# dc-dc.net
KiCad netlist of a schematic drawn in Altium Designer
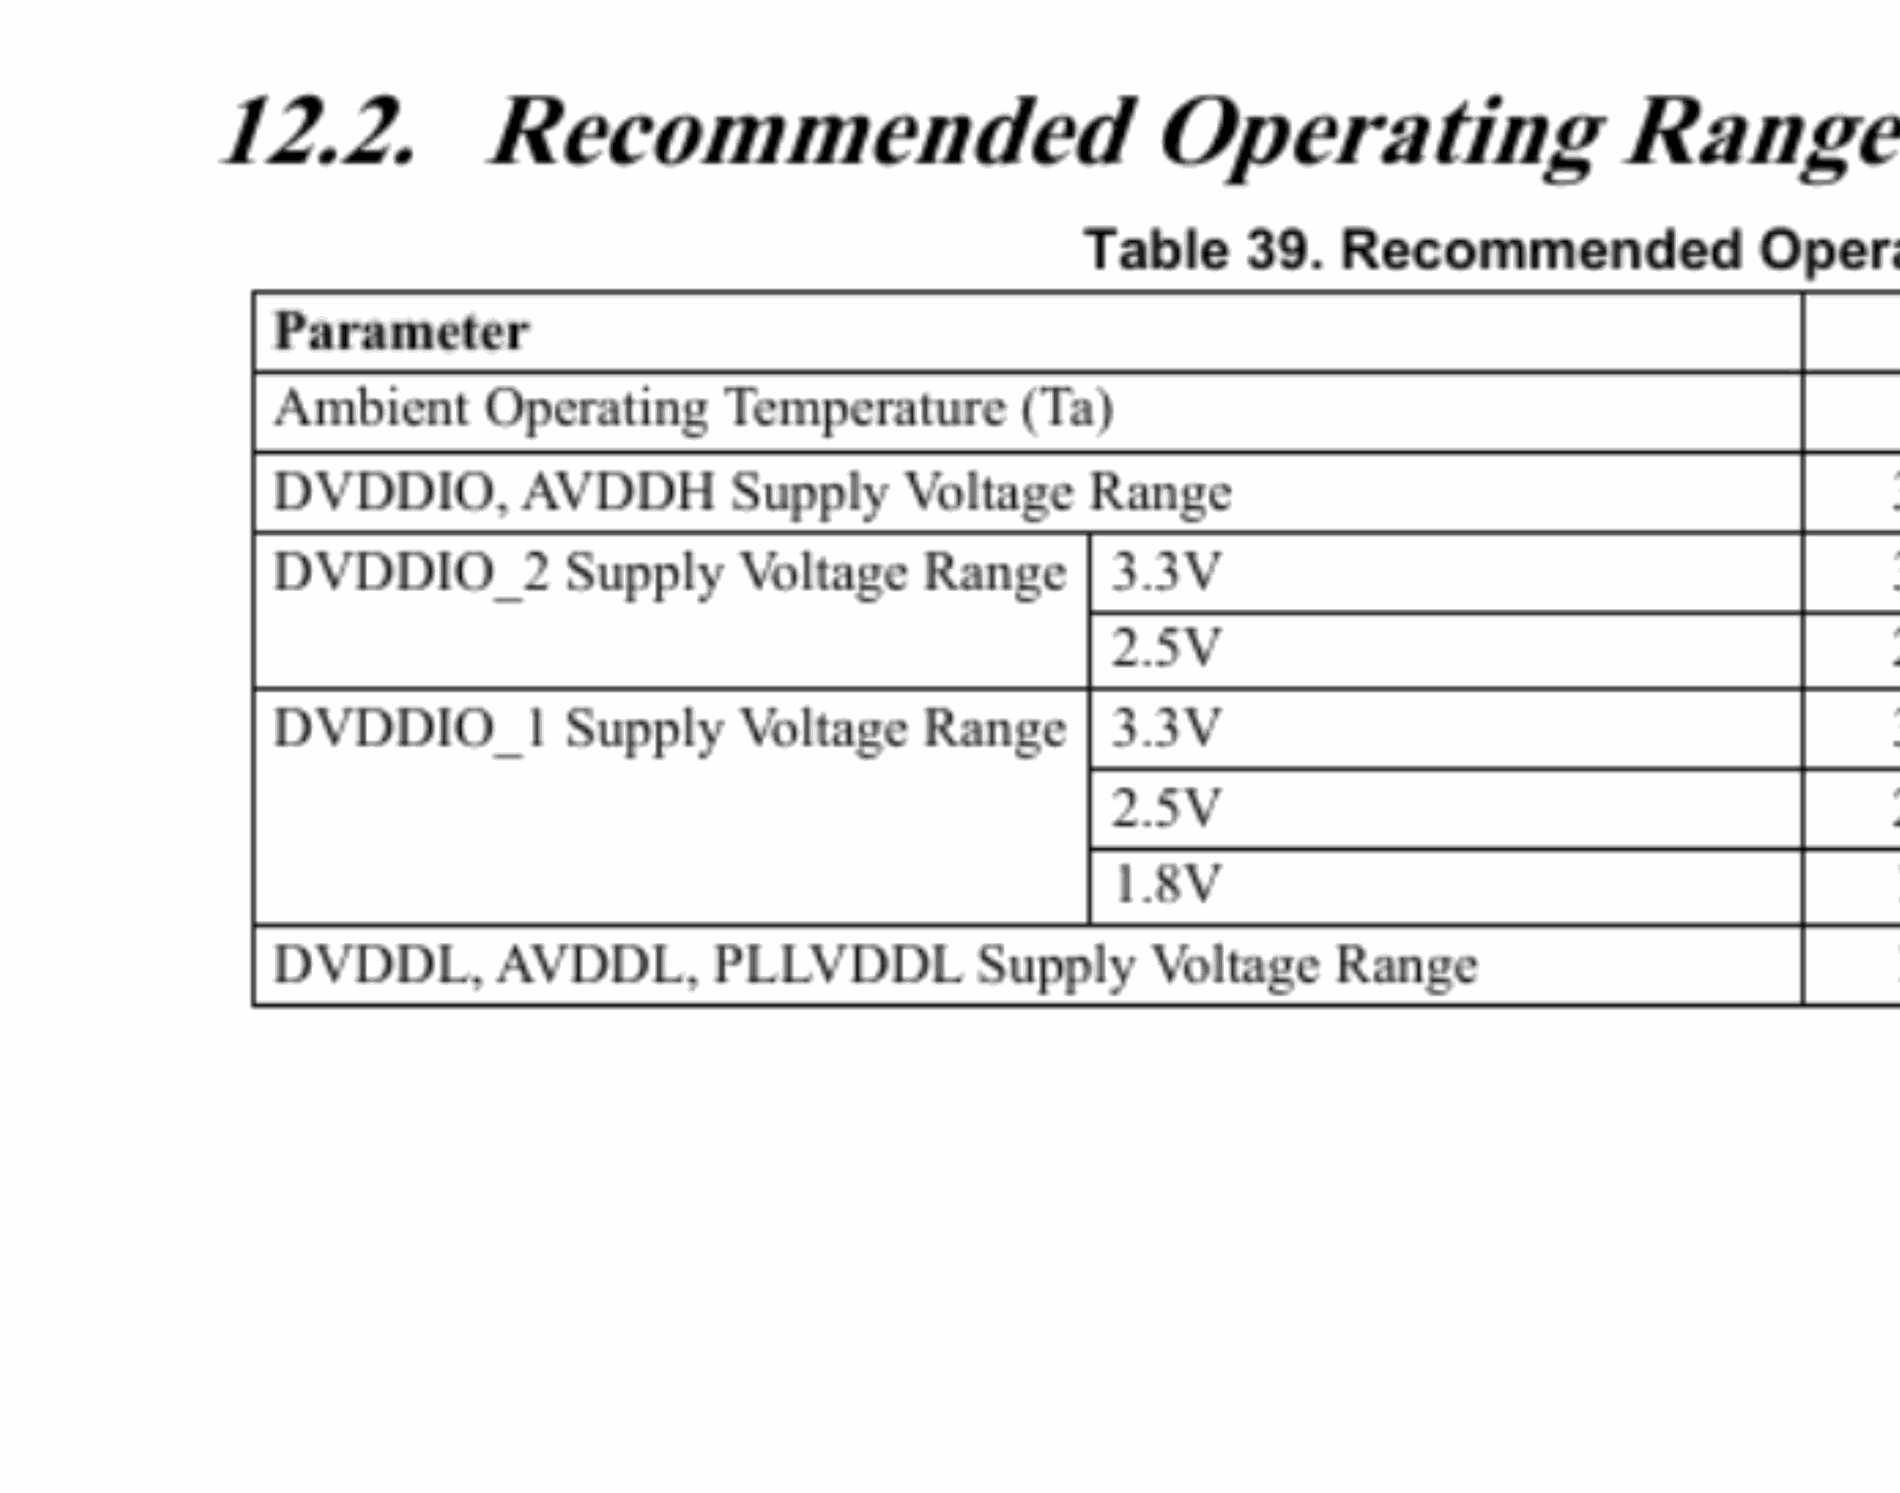
[diagram p0: dc-dc.SchDoc, top left]
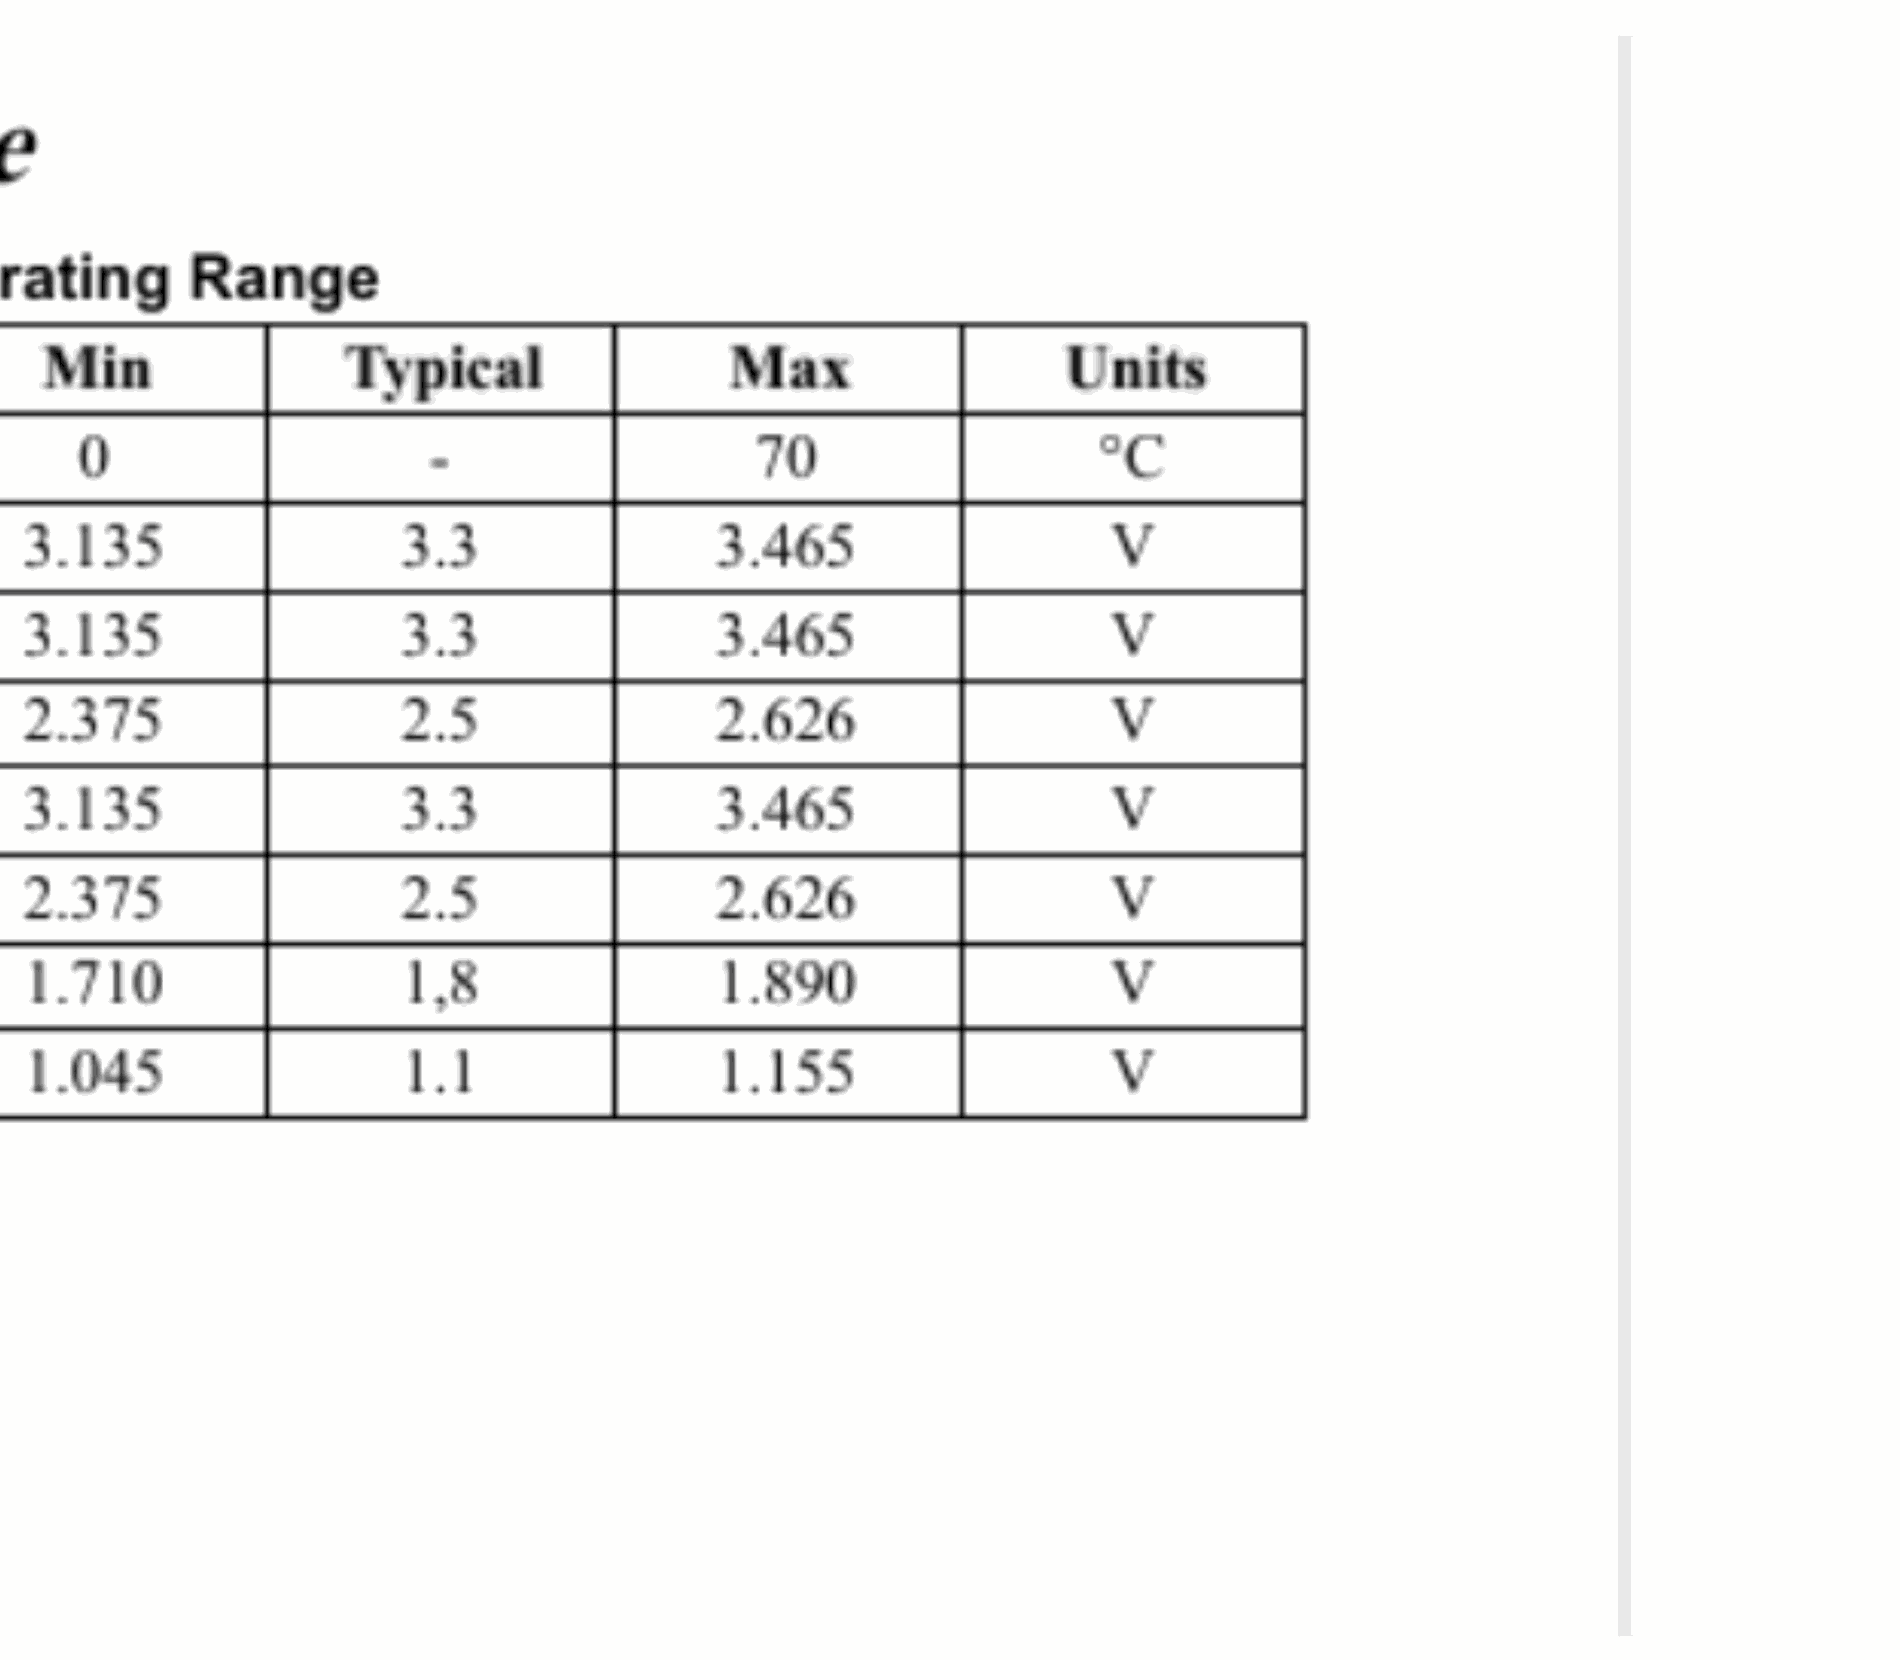
[diagram p1: dc-dc.SchDoc, top right]
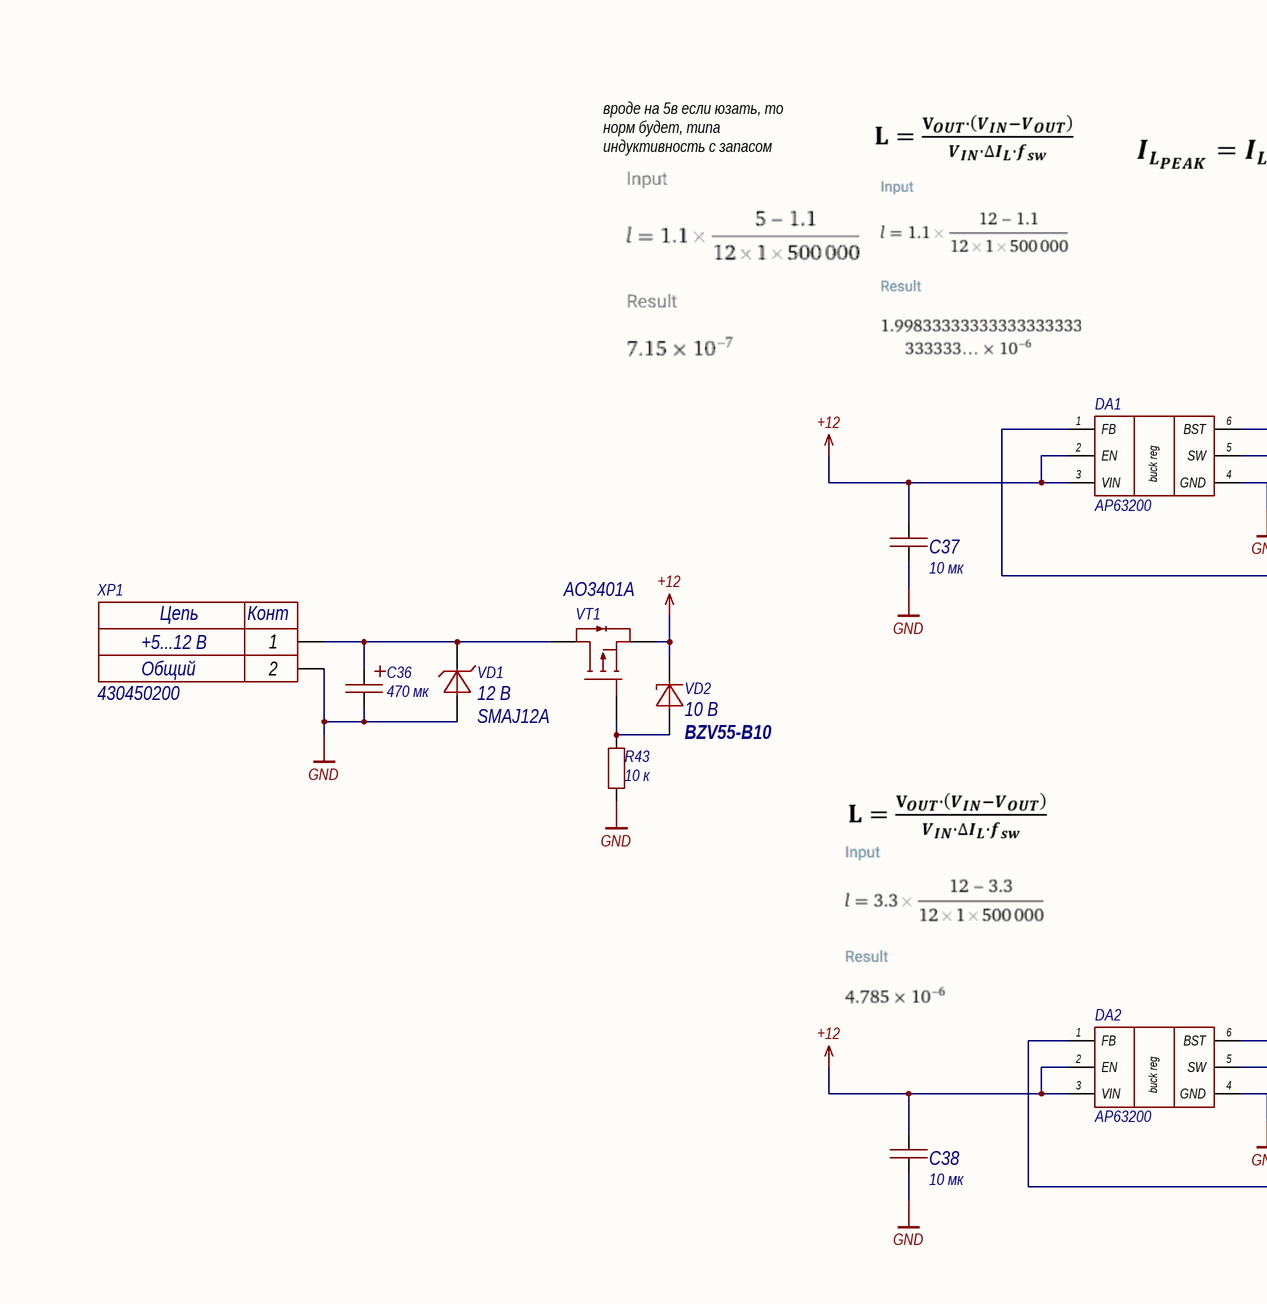
[diagram p2: dc-dc.SchDoc, bottom left]
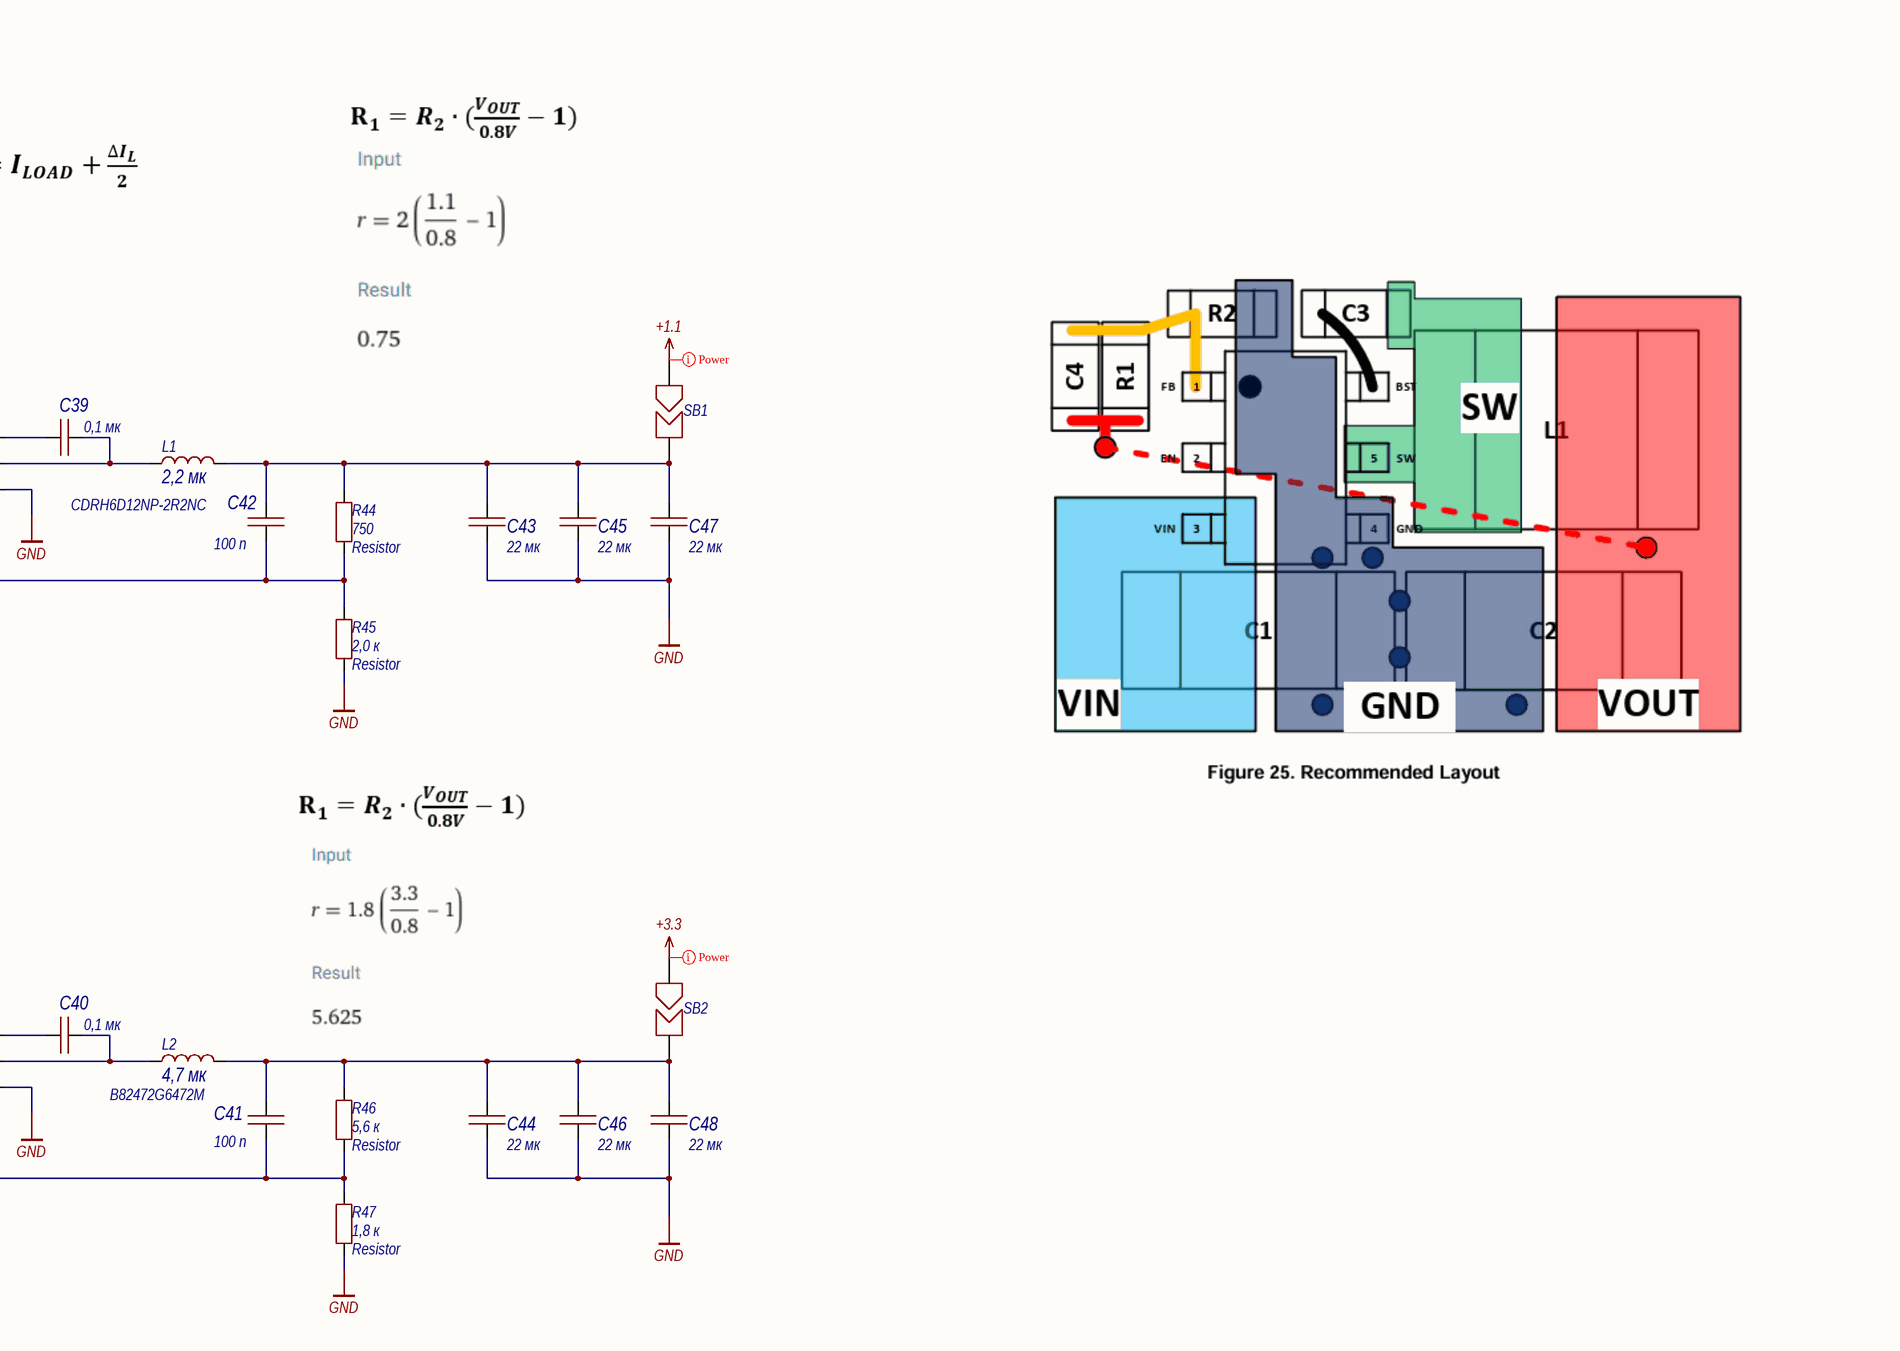
[diagram p3: dc-dc.SchDoc, bottom right]

(export (version "E")
  (design (tool "Eeschema 10.0.6"))
  (components
    (comp (ref "C36")
      (value "470 мк")
      (footprint "ECAP_SMD_10,3x10,3")
      (description "Конденсатор алюминиевый электролитический 470мкФ 16В ±20% (10х10)мм SMD 460мА 2000часов 105°C")
      (fields
        (field (name "PART NUMBER") "CK016M471G10PKKKV00R")
        (field (name "TOLERANCE") "20")
        (field (name "АВТОР") "rreali")
      )
      (libsource (lib "Hydrolib") (part "Capacitor_polar"))
    )
    (comp (ref "C37")
      (value "10 мк")
      (footprint "1210C")
      (description "Конденсатор 1210C ёмкостью 10 мк 10%, 35 В, X7R")
      (fields (field (name "PART NUMBER") "Capacitor_10u_10_35V_X7R_1210C") (field (name "TOLERANCE") "10%"))
      (libsource (lib "Hydrolib") (part "Capacitor"))
    )
    (comp (ref "C38")
      (value "10 мк")
      (footprint "1210C")
      (description "Конденсатор 1210C ёмкостью 10 мк 10%, 35 В, X7R")
      (fields (field (name "PART NUMBER") "Capacitor_10u_10_35V_X7R_1210C") (field (name "TOLERANCE") "10%"))
      (libsource (lib "Hydrolib") (part "Capacitor"))
    )
    (comp (ref "C39")
      (value "0,1 мк")
      (footprint "0603C")
      (description "Конденсатор 0603C ёмкостью 0,1 мк 10%, 50 В, X7R")
      (fields (field (name "PART NUMBER") "Capacitor_0,1u_10_50V_X7R_0603C") (field (name "TOLERANCE") "10%"))
      (libsource (lib "Hydrolib") (part "Capacitor"))
    )
    (comp (ref "C40")
      (value "0,1 мк")
      (footprint "0603C")
      (description "Конденсатор 0603C ёмкостью 0,1 мк 10%, 50 В, X7R")
      (fields (field (name "PART NUMBER") "Capacitor_0,1u_10_50V_X7R_0603C") (field (name "TOLERANCE") "10%"))
      (libsource (lib "Hydrolib") (part "Capacitor"))
    )
    (comp (ref "C41")
      (value "100 п")
      (footprint "0603C")
      (description "Конденсатор 0603C ёмкостью 100 п 10%, 50 В, X7R")
      (fields (field (name "PART NUMBER") "Capacitor_100p_10_50V_X7R_0603C") (field (name "TOLERANCE") "10%"))
      (libsource (lib "Hydrolib") (part "Capacitor"))
    )
    (comp (ref "C42")
      (value "100 п")
      (footprint "0603C")
      (description "Конденсатор 0603C ёмкостью 100 п 10%, 50 В, X7R")
      (fields (field (name "PART NUMBER") "Capacitor_100p_10_50V_X7R_0603C") (field (name "TOLERANCE") "10%"))
      (libsource (lib "Hydrolib") (part "Capacitor"))
    )
    (comp (ref "C43")
      (value "22 мк")
      (footprint "1210C")
      (description "Конденсатор 1210C ёмкостью 22 мк 10%, 25 В, X7R")
      (fields (field (name "PART NUMBER") "Capacitor_22u_10_25V_X7R_1210C") (field (name "TOLERANCE") "10%"))
      (libsource (lib "Hydrolib") (part "Capacitor"))
    )
    (comp (ref "C44")
      (value "22 мк")
      (footprint "1210C")
      (description "Конденсатор 1210C ёмкостью 22 мк 10%, 25 В, X7R")
      (fields (field (name "PART NUMBER") "Capacitor_22u_10_25V_X7R_1210C") (field (name "TOLERANCE") "10%"))
      (libsource (lib "Hydrolib") (part "Capacitor"))
    )
    (comp (ref "C45")
      (value "22 мк")
      (footprint "1210C")
      (description "Конденсатор 1210C ёмкостью 22 мк 10%, 25 В, X7R")
      (fields (field (name "PART NUMBER") "Capacitor_22u_10_25V_X7R_1210C") (field (name "TOLERANCE") "10%"))
      (libsource (lib "Hydrolib") (part "Capacitor"))
    )
    (comp (ref "C46")
      (value "22 мк")
      (footprint "1210C")
      (description "Конденсатор 1210C ёмкостью 22 мк 10%, 25 В, X7R")
      (fields (field (name "PART NUMBER") "Capacitor_22u_10_25V_X7R_1210C") (field (name "TOLERANCE") "10%"))
      (libsource (lib "Hydrolib") (part "Capacitor"))
    )
    (comp (ref "C47")
      (value "22 мк")
      (footprint "1210C")
      (description "Конденсатор 1210C ёмкостью 22 мк 10%, 25 В, X7R")
      (fields (field (name "PART NUMBER") "Capacitor_22u_10_25V_X7R_1210C") (field (name "TOLERANCE") "10%"))
      (libsource (lib "Hydrolib") (part "Capacitor"))
    )
    (comp (ref "C48")
      (value "22 мк")
      (footprint "1210C")
      (description "Конденсатор 1210C ёмкостью 22 мк 10%, 25 В, X7R")
      (fields (field (name "PART NUMBER") "Capacitor_22u_10_25V_X7R_1210C") (field (name "TOLERANCE") "10%"))
      (libsource (lib "Hydrolib") (part "Capacitor"))
    )
    (comp (ref "DA1")
      (value "AP63200")
      (footprint "TSOT26")
      (description "DC-DC понижающий преобразователь, Vin: 3.8 - 40 В, adj, 2 А")
      (libsource (lib "Hydrolib") (part "AP63200"))
    )
    (comp (ref "DA2")
      (value "AP63200")
      (footprint "TSOT26")
      (description "DC-DC понижающий преобразователь, Vin: 3.8 - 40 В, adj, 2 А")
      (libsource (lib "Hydrolib") (part "AP63200"))
    )
    (comp (ref "L1")
      (value "CDRH6D12NP-2R2NC")
      (footprint "CDRH6D12")
      (description "Индуктивность на 2,2 мкГн, номинальный ток 2,5 А")
      (fields (field (name "ALTIUM_VALUE") "2,2 мк") (field (name "АВТОР") "rreali"))
      (libsource (lib "Hydrolib") (part "Inductance_1-3"))
    )
    (comp (ref "L2")
      (value "B82472G6472M")
      (footprint "B82462G4")
      (description "Индуктивность на 4,7 мкГн, номинальный ток 2,5 А")
      (fields (field (name "ALTIUM_VALUE") "4,7 мк") (field (name "АВТОР") "rreali"))
      (libsource (lib "Hydrolib") (part "Inductance"))
    )
    (comp (ref "R43")
      (value "10 к")
      (footprint "0603R")
      (description "Резистор номиналом 10 кОм 1%")
      (fields (field (name "PART NUMBER") "Resistor_10k_1_0603") (field (name "TOLERANCE") "1%"))
      (libsource (lib "Hydrolib") (part "Resistor"))
    )
    (comp (ref "R44")
      (value "Resistor")
      (footprint "0603R")
      (description "Резистор номиналом 750 Ом 1%")
      (fields
        (field (name "ALTIUM_VALUE") "750")
        (field (name "PART NUMBER") "Resistor_750_1_0603")
        (field (name "TOLERANCE") "1%")
      )
      (libsource (lib "Hydrolib") (part "Resistor"))
    )
    (comp (ref "R45")
      (value "Resistor")
      (footprint "0603R")
      (description "Резистор номиналом 2,0 кОм 1%")
      (fields
        (field (name "ALTIUM_VALUE") "2,0 к")
        (field (name "PART NUMBER") "Resistor_2.0k_1_0603")
        (field (name "TOLERANCE") "1%")
      )
      (libsource (lib "Hydrolib") (part "Resistor"))
    )
    (comp (ref "R46")
      (value "Resistor")
      (footprint "0603R")
      (description "Резистор номиналом 5,6 кОм 1%")
      (fields
        (field (name "ALTIUM_VALUE") "5,6 к")
        (field (name "PART NUMBER") "Resistor_5.6k_1_0603")
        (field (name "TOLERANCE") "1%")
      )
      (libsource (lib "Hydrolib") (part "Resistor"))
    )
    (comp (ref "R47")
      (value "Resistor")
      (footprint "0603R")
      (description "Резистор номиналом 1,8 кОм 1%")
      (fields
        (field (name "ALTIUM_VALUE") "1,8 к")
        (field (name "PART NUMBER") "Resistor_1.8k_1_0603")
        (field (name "TOLERANCE") "1%")
      )
      (libsource (lib "Hydrolib") (part "Resistor"))
    )
    (comp (ref "SB1")
      (value "SB")
      (footprint "0805SB")
      (description "Solder bridge, мост припоя, запаиваемая перемычка, net tie, jumper")
      (fields (field (name "АВТОР") "rreali"))
      (libsource (lib "Hydrolib") (part "SB"))
    )
    (comp (ref "SB2")
      (value "SB")
      (footprint "0805SB")
      (description "Solder bridge, мост припоя, запаиваемая перемычка, net tie, jumper")
      (fields (field (name "АВТОР") "rreali"))
      (libsource (lib "Hydrolib") (part "SB"))
    )
    (comp (ref "VD1")
      (value "SMAJ12A")
      (footprint "SMA")
      (description "Защитный диод на 12 В, рассеиваемая мощность 400 Вт")
      (fields (field (name "ALTIUM_VALUE") "12 В") (field (name "АВТОР") "rreali"))
      (libsource (lib "Hydrolib") (part "TVS_1_1dir"))
    )
    (comp (ref "VD2")
      (value "BZV55-B10")
      (footprint "mini_MELF_3.5mm")
      (description "Стабилитрон 10В, 2%, 0.5Вт")
      (fields (field (name "ALTIUM_VALUE") "10 В") (field (name "АВТОР") "rreali"))
      (libsource (lib "Hydrolib") (part "Zener"))
    )
    (comp (ref "VT1")
      (value "AO3401A")
      (footprint "SOT23-3")
      (description "P-канальный MOSFET")
      (libsource (lib "Hydrolib") (part "MOSFET P-channel 2"))
    )
    (comp (ref "XP1")
      (value "430450200")
      (footprint "MOLEX_MICRO-FIT_430450200")
      (fields
        (field (name "VALUE2") "Общий")
        (field (name "VALUE1") "+5...12 В")
        (field (name "АВТОР") "rreali")
      )
      (libsource (lib "Hydrolib") (part "Conn_2pin"))
    )
  )
  (nets
    (net (code "1") (name "+1.1") (class "Default")
      (node (ref "SB1") (pin "1") (pinfunction "1_1") (pintype "passive"))
    )
    (net (code "2") (name "+3.3") (class "Default")
      (node (ref "SB2") (pin "1") (pinfunction "1_1") (pintype "passive"))
    )
    (net (code "3") (name "+12") (class "Default")
      (node (ref "C37") (pin "2") (pinfunction "2_2") (pintype "passive"))
      (node (ref "C38") (pin "2") (pinfunction "2_2") (pintype "passive"))
      (node (ref "DA1") (pin "2") (pinfunction "EN_2") (pintype "passive"))
      (node (ref "DA1") (pin "3") (pinfunction "VIN_3") (pintype "passive"))
      (node (ref "DA2") (pin "2") (pinfunction "EN_2") (pintype "passive"))
      (node (ref "DA2") (pin "3") (pinfunction "VIN_3") (pintype "passive"))
      (node (ref "VD2") (pin "2") (pinfunction "2_2") (pintype "passive"))
      (node (ref "VT1") (pin "2") (pinfunction "2_2") (pintype "passive"))
    )
    (net (code "4") (name "GND") (class "Default")
      (node (ref "C36") (pin "2") (pinfunction "2_2") (pintype "passive"))
      (node (ref "C37") (pin "1") (pinfunction "1_1") (pintype "passive"))
      (node (ref "C38") (pin "1") (pinfunction "1_1") (pintype "passive"))
      (node (ref "C43") (pin "1") (pinfunction "1_1") (pintype "passive"))
      (node (ref "C44") (pin "1") (pinfunction "1_1") (pintype "passive"))
      (node (ref "C45") (pin "1") (pinfunction "1_1") (pintype "passive"))
      (node (ref "C46") (pin "1") (pinfunction "1_1") (pintype "passive"))
      (node (ref "C47") (pin "1") (pinfunction "1_1") (pintype "passive"))
      (node (ref "C48") (pin "1") (pinfunction "1_1") (pintype "passive"))
      (node (ref "DA1") (pin "4") (pinfunction "GND_4") (pintype "passive"))
      (node (ref "DA2") (pin "4") (pinfunction "GND_4") (pintype "passive"))
      (node (ref "R43") (pin "1") (pinfunction "1_1") (pintype "passive"))
      (node (ref "R45") (pin "1") (pinfunction "1_1") (pintype "passive"))
      (node (ref "R47") (pin "1") (pinfunction "1_1") (pintype "passive"))
      (node (ref "VD1") (pin "1") (pinfunction "1_1") (pintype "passive"))
      (node (ref "XP1") (pin "2") (pinfunction "2_2") (pintype "passive"))
    )
    (net (code "5") (name "Net-(C36-Pad1)") (class "Default")
      (node (ref "C36") (pin "1") (pinfunction "1_1") (pintype "passive"))
      (node (ref "VD1") (pin "2") (pinfunction "2_2") (pintype "passive"))
      (node (ref "VT1") (pin "3") (pinfunction "3_3") (pintype "passive"))
      (node (ref "XP1") (pin "1") (pinfunction "1_1") (pintype "passive"))
    )
    (net (code "6") (name "Net-(C41-Pad2)") (class "Default")
      (node (ref "C41") (pin "2") (pinfunction "2_2") (pintype "passive"))
      (node (ref "C44") (pin "2") (pinfunction "2_2") (pintype "passive"))
      (node (ref "C46") (pin "2") (pinfunction "2_2") (pintype "passive"))
      (node (ref "C48") (pin "2") (pinfunction "2_2") (pintype "passive"))
      (node (ref "L2") (pin "2") (pinfunction "2_2") (pintype "passive"))
      (node (ref "R46") (pin "2") (pinfunction "2_2") (pintype "passive"))
      (node (ref "SB2") (pin "2") (pinfunction "2_2") (pintype "passive"))
    )
    (net (code "7") (name "Net-(C42-Pad2)") (class "Default")
      (node (ref "C42") (pin "2") (pinfunction "2_2") (pintype "passive"))
      (node (ref "C43") (pin "2") (pinfunction "2_2") (pintype "passive"))
      (node (ref "C45") (pin "2") (pinfunction "2_2") (pintype "passive"))
      (node (ref "C47") (pin "2") (pinfunction "2_2") (pintype "passive"))
      (node (ref "L1") (pin "3") (pinfunction "3_3") (pintype "passive"))
      (node (ref "R44") (pin "2") (pinfunction "2_2") (pintype "passive"))
      (node (ref "SB1") (pin "2") (pinfunction "2_2") (pintype "passive"))
    )
    (net (code "8") (name "Net-(DA1-BST)") (class "Default")
      (node (ref "C39") (pin "1") (pinfunction "1_1") (pintype "passive"))
      (node (ref "DA1") (pin "6") (pinfunction "BST_6") (pintype "passive"))
    )
    (net (code "9") (name "Net-(DA1-FB)") (class "Default")
      (node (ref "C42") (pin "1") (pinfunction "1_1") (pintype "passive"))
      (node (ref "DA1") (pin "1") (pinfunction "FB_1") (pintype "passive"))
      (node (ref "R44") (pin "1") (pinfunction "1_1") (pintype "passive"))
      (node (ref "R45") (pin "2") (pinfunction "2_2") (pintype "passive"))
    )
    (net (code "10") (name "Net-(DA1-SW)") (class "Default")
      (node (ref "C39") (pin "2") (pinfunction "2_2") (pintype "passive"))
      (node (ref "DA1") (pin "5") (pinfunction "SW_5") (pintype "passive"))
      (node (ref "L1") (pin "1") (pinfunction "1_1") (pintype "passive"))
    )
    (net (code "11") (name "Net-(DA2-BST)") (class "Default")
      (node (ref "C40") (pin "1") (pinfunction "1_1") (pintype "passive"))
      (node (ref "DA2") (pin "6") (pinfunction "BST_6") (pintype "passive"))
    )
    (net (code "12") (name "Net-(DA2-FB)") (class "Default")
      (node (ref "C41") (pin "1") (pinfunction "1_1") (pintype "passive"))
      (node (ref "DA2") (pin "1") (pinfunction "FB_1") (pintype "passive"))
      (node (ref "R46") (pin "1") (pinfunction "1_1") (pintype "passive"))
      (node (ref "R47") (pin "2") (pinfunction "2_2") (pintype "passive"))
    )
    (net (code "13") (name "Net-(DA2-SW)") (class "Default")
      (node (ref "C40") (pin "2") (pinfunction "2_2") (pintype "passive"))
      (node (ref "DA2") (pin "5") (pinfunction "SW_5") (pintype "passive"))
      (node (ref "L2") (pin "1") (pinfunction "1_1") (pintype "passive"))
    )
    (net (code "14") (name "Net-(R43-Pad2)") (class "Default")
      (node (ref "R43") (pin "2") (pinfunction "2_2") (pintype "passive"))
      (node (ref "VD2") (pin "1") (pinfunction "1_1") (pintype "passive"))
      (node (ref "VT1") (pin "1") (pinfunction "1_1") (pintype "passive"))
    )
  )
)
